# J201M1_MOS_TEST.net
KiCad netlist of a schematic drawn in Altium Designer
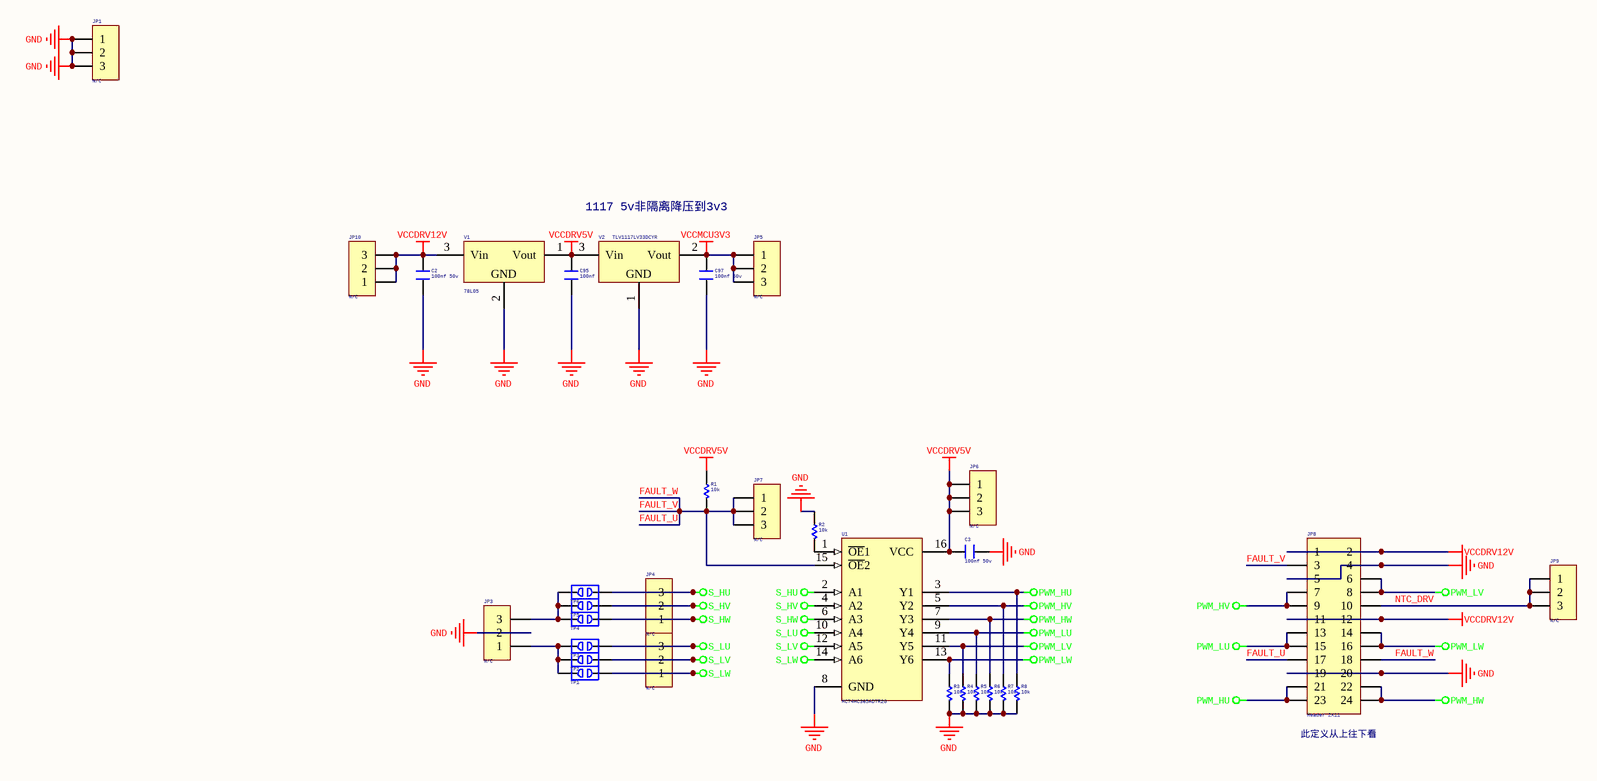
[diagram p0: J201M1_MOS_TEST.SchDoc]

(export (version "E")
  (design (tool "Eeschema 10.0.6"))
  (components
    (comp (ref "C2")
      (value "100nf 50v")
      (footprint "C 0603")
      (description "无极性贴片电容")
      (fields (field (name "VOLTAGE") "50v"))
      (libsource (lib "电阻-电容-电感") (part "C"))
    )
    (comp (ref "C3")
      (value "100nf 50v")
      (footprint "C 0603")
      (description "无极性贴片电容")
      (fields (field (name "VOLTAGE") "50v"))
      (libsource (lib "电阻-电容-电感") (part "C"))
    )
    (comp (ref "C95")
      (value "100nf 50v")
      (footprint "C 0603")
      (description "无极性贴片电容")
      (fields (field (name "VOLTAGE") "50v"))
      (libsource (lib "电阻-电容-电感") (part "C"))
    )
    (comp (ref "C97")
      (value "100nf 50v")
      (footprint "C 0603")
      (description "无极性贴片电容")
      (fields (field (name "VOLTAGE") "50v"))
      (libsource (lib "电阻-电容-电感") (part "C"))
    )
    (comp (ref "JP1")
      (value "N/C")
      (footprint "HDR-1X3")
      (description "3P接插件")
      (libsource (lib "") (part "Header 3_1"))
    )
    (comp (ref "JP2")
      (value "N/C")
      (footprint "HDR-1X3")
      (description "3P接插件")
      (libsource (lib "接插件") (part "Header 3"))
    )
    (comp (ref "JP3")
      (value "N/C")
      (footprint "HDR-1X3")
      (description "3P接插件")
      (libsource (lib "接插件") (part "Header 3"))
    )
    (comp (ref "JP4")
      (value "N/C")
      (footprint "HDR-1X3")
      (description "3P接插件")
      (libsource (lib "接插件") (part "Header 3"))
    )
    (comp (ref "JP5")
      (value "N/C")
      (footprint "HDR-1X3")
      (description "3P接插件")
      (libsource (lib "") (part "Header 3_1"))
    )
    (comp (ref "JP6")
      (value "N/C")
      (footprint "HDR-1X3")
      (description "3P接插件")
      (libsource (lib "") (part "Header 3_1"))
    )
    (comp (ref "JP7")
      (value "N/C")
      (footprint "HDR-1X3")
      (description "3P接插件")
      (libsource (lib "") (part "Header 3_1"))
    )
    (comp (ref "JP8")
      (value "Header 2X11")
      (footprint "HDR-12X2")
      (description "12*2P接插件")
      (libsource (lib "接插件") (part "Header 12X2"))
    )
    (comp (ref "JP9")
      (value "N/C")
      (footprint "HDR-1X3")
      (description "3P接插件")
      (libsource (lib "") (part "Header 3_1"))
    )
    (comp (ref "JP10")
      (value "N/C")
      (footprint "HDR-1X3")
      (description "3P接插件")
      (libsource (lib "接插件") (part "Header 3"))
    )
    (comp (ref "R1")
      (value "10k")
      (footprint "R 0805")
      (description "贴片电阻")
      (libsource (lib "电阻-电容-电感") (part "R"))
    )
    (comp (ref "R2")
      (value "10k")
      (footprint "R 0805")
      (description "贴片电阻")
      (libsource (lib "电阻-电容-电感") (part "R"))
    )
    (comp (ref "R3")
      (value "10k")
      (footprint "R 0805")
      (description "贴片电阻")
      (libsource (lib "电阻-电容-电感") (part "R"))
    )
    (comp (ref "R4")
      (value "10k")
      (footprint "R 0805")
      (description "贴片电阻")
      (libsource (lib "电阻-电容-电感") (part "R"))
    )
    (comp (ref "R5")
      (value "10k")
      (footprint "R 0805")
      (description "贴片电阻")
      (libsource (lib "电阻-电容-电感") (part "R"))
    )
    (comp (ref "R6")
      (value "10k")
      (footprint "R 0805")
      (description "贴片电阻")
      (libsource (lib "电阻-电容-电感") (part "R"))
    )
    (comp (ref "R7")
      (value "10k")
      (footprint "R 0805")
      (description "贴片电阻")
      (libsource (lib "电阻-电容-电感") (part "R"))
    )
    (comp (ref "R8")
      (value "10k")
      (footprint "R 0805")
      (description "贴片电阻")
      (libsource (lib "电阻-电容-电感") (part "R"))
    )
    (comp (ref "TP1")
      (value "DEBUG PAD")
      (footprint "DEBUG PAD 0603")
      (description "调试断点焊盘")
      (libsource (lib "未分类器件") (part "DEBUG"))
    )
    (comp (ref "TP2")
      (value "DEBUG PAD")
      (footprint "DEBUG PAD 0603")
      (description "调试断点焊盘")
      (libsource (lib "未分类器件") (part "DEBUG"))
    )
    (comp (ref "TP3")
      (value "DEBUG PAD")
      (footprint "DEBUG PAD 0603")
      (description "调试断点焊盘")
      (libsource (lib "未分类器件") (part "DEBUG"))
    )
    (comp (ref "TP4")
      (value "DEBUG PAD")
      (footprint "DEBUG PAD 0603")
      (description "调试断点焊盘")
      (libsource (lib "未分类器件") (part "DEBUG"))
    )
    (comp (ref "TP5")
      (value "DEBUG PAD")
      (footprint "DEBUG PAD 0603")
      (description "调试断点焊盘")
      (libsource (lib "未分类器件") (part "DEBUG"))
    )
    (comp (ref "TP6")
      (value "DEBUG PAD")
      (footprint "DEBUG PAD 0603")
      (description "调试断点焊盘")
      (libsource (lib "未分类器件") (part "DEBUG"))
    )
    (comp (ref "U1")
      (value "MC74HC365ADTR2G")
      (footprint "TSSOP16_L")
      (description "6路缓冲器")
      (libsource (lib "74系列芯片") (part "SN74HC365D"))
    )
    (comp (ref "V1")
      (value "78L05")
      (footprint "SOT89_M")
      (description "SOT89线性稳压芯片")
      (libsource (lib "IC芯片") (part "78LXX"))
    )
    (comp (ref "V2")
      (value "TLV1117LV33DCYR")
      (footprint "SOT223_L")
      (description "三端稳压芯片")
      (libsource (lib "IC芯片") (part "AMS1117"))
    )
  )
  (nets
    (net (code "1") (name "/FAULT_U") (class "Default")
      (node (ref "JP7") (pin "1") (pinfunction "1_1") (pintype "passive"))
      (node (ref "JP7") (pin "2") (pinfunction "2_2") (pintype "passive"))
      (node (ref "JP7") (pin "3") (pinfunction "3_3") (pintype "passive"))
      (node (ref "JP8") (pin "17") (pinfunction "17_17") (pintype "passive"))
      (node (ref "JP8") (pin "18") (pinfunction "18_18") (pintype "passive"))
      (node (ref "JP8") (pin "3") (pinfunction "3_3") (pintype "passive"))
      (node (ref "R1") (pin "2") (pinfunction "2_2") (pintype "passive"))
      (node (ref "U1") (pin "15") (pinfunction "~{OE}2_15") (pintype "input"))
    )
    (net (code "2") (name "/NTC_DRV") (class "Default")
      (node (ref "JP8") (pin "10") (pinfunction "10_10") (pintype "passive"))
      (node (ref "JP9") (pin "1") (pinfunction "1_1") (pintype "passive"))
      (node (ref "JP9") (pin "2") (pinfunction "2_2") (pintype "passive"))
      (node (ref "JP9") (pin "3") (pinfunction "3_3") (pintype "passive"))
    )
    (net (code "3") (name "GND") (class "Default")
      (node (ref "C2") (pin "2") (pinfunction "2_2") (pintype "passive"))
      (node (ref "C3") (pin "2") (pinfunction "2_2") (pintype "passive"))
      (node (ref "C95") (pin "2") (pinfunction "2_2") (pintype "passive"))
      (node (ref "C97") (pin "2") (pinfunction "2_2") (pintype "passive"))
      (node (ref "JP1") (pin "1") (pinfunction "1_1") (pintype "passive"))
      (node (ref "JP1") (pin "2") (pinfunction "2_2") (pintype "passive"))
      (node (ref "JP1") (pin "3") (pinfunction "3_3") (pintype "passive"))
      (node (ref "JP3") (pin "2") (pinfunction "2_2") (pintype "passive"))
      (node (ref "JP8") (pin "19") (pinfunction "19_19") (pintype "passive"))
      (node (ref "JP8") (pin "20") (pinfunction "20_20") (pintype "passive"))
      (node (ref "JP8") (pin "4") (pinfunction "4_4") (pintype "passive"))
      (node (ref "JP8") (pin "5") (pinfunction "5_5") (pintype "passive"))
      (node (ref "R2") (pin "1") (pinfunction "1_1") (pintype "passive"))
      (node (ref "R3") (pin "2") (pinfunction "2_2") (pintype "passive"))
      (node (ref "R4") (pin "2") (pinfunction "2_2") (pintype "passive"))
      (node (ref "R5") (pin "2") (pinfunction "2_2") (pintype "passive"))
      (node (ref "R6") (pin "2") (pinfunction "2_2") (pintype "passive"))
      (node (ref "R7") (pin "2") (pinfunction "2_2") (pintype "passive"))
      (node (ref "R8") (pin "2") (pinfunction "2_2") (pintype "passive"))
      (node (ref "U1") (pin "8") (pinfunction "GND_8") (pintype "power_in"))
      (node (ref "V1") (pin "2") (pinfunction "GND_2") (pintype "passive"))
      (node (ref "V2") (pin "1") (pinfunction "GND_1") (pintype "passive"))
    )
    (net (code "4") (name "Net-(JP3-Pad1)") (class "Default")
      (node (ref "JP3") (pin "1") (pinfunction "1_1") (pintype "passive"))
      (node (ref "TP1") (pin "2") (pinfunction "2_2") (pintype "passive"))
      (node (ref "TP2") (pin "2") (pinfunction "2_2") (pintype "passive"))
      (node (ref "TP3") (pin "2") (pinfunction "2_2") (pintype "passive"))
    )
    (net (code "5") (name "Net-(JP3-Pad3)") (class "Default")
      (node (ref "JP3") (pin "3") (pinfunction "3_3") (pintype "passive"))
      (node (ref "TP4") (pin "2") (pinfunction "2_2") (pintype "passive"))
      (node (ref "TP5") (pin "2") (pinfunction "2_2") (pintype "passive"))
      (node (ref "TP6") (pin "2") (pinfunction "2_2") (pintype "passive"))
    )
    (net (code "6") (name "Net-(U1-~{OE}1)") (class "Default")
      (node (ref "R2") (pin "2") (pinfunction "2_2") (pintype "passive"))
      (node (ref "U1") (pin "1") (pinfunction "~{OE}1_1") (pintype "input"))
    )
    (net (code "7") (name "PWM_HU") (class "Default")
      (node (ref "JP8") (pin "21") (pinfunction "21_21") (pintype "passive"))
      (node (ref "JP8") (pin "23") (pinfunction "23_23") (pintype "passive"))
      (node (ref "R8") (pin "1") (pinfunction "1_1") (pintype "passive"))
      (node (ref "U1") (pin "3") (pinfunction "Y1_3") (pintype "tri_state"))
    )
    (net (code "8") (name "PWM_HV") (class "Default")
      (node (ref "JP8") (pin "7") (pinfunction "7_7") (pintype "passive"))
      (node (ref "JP8") (pin "9") (pinfunction "9_9") (pintype "passive"))
      (node (ref "R7") (pin "1") (pinfunction "1_1") (pintype "passive"))
      (node (ref "U1") (pin "5") (pinfunction "Y2_5") (pintype "tri_state"))
    )
    (net (code "9") (name "PWM_HW") (class "Default")
      (node (ref "JP8") (pin "22") (pinfunction "22_22") (pintype "passive"))
      (node (ref "JP8") (pin "24") (pinfunction "24_24") (pintype "passive"))
      (node (ref "R6") (pin "1") (pinfunction "1_1") (pintype "passive"))
      (node (ref "U1") (pin "7") (pinfunction "Y3_7") (pintype "tri_state"))
    )
    (net (code "10") (name "PWM_LU") (class "Default")
      (node (ref "JP8") (pin "13") (pinfunction "13_13") (pintype "passive"))
      (node (ref "JP8") (pin "15") (pinfunction "15_15") (pintype "passive"))
      (node (ref "R5") (pin "1") (pinfunction "1_1") (pintype "passive"))
      (node (ref "U1") (pin "9") (pinfunction "Y4_9") (pintype "tri_state"))
    )
    (net (code "11") (name "PWM_LV") (class "Default")
      (node (ref "JP8") (pin "6") (pinfunction "6_6") (pintype "passive"))
      (node (ref "JP8") (pin "8") (pinfunction "8_8") (pintype "passive"))
      (node (ref "R4") (pin "1") (pinfunction "1_1") (pintype "passive"))
      (node (ref "U1") (pin "11") (pinfunction "Y5_11") (pintype "tri_state"))
    )
    (net (code "12") (name "PWM_LW") (class "Default")
      (node (ref "JP8") (pin "14") (pinfunction "14_14") (pintype "passive"))
      (node (ref "JP8") (pin "16") (pinfunction "16_16") (pintype "passive"))
      (node (ref "R3") (pin "1") (pinfunction "1_1") (pintype "passive"))
      (node (ref "U1") (pin "13") (pinfunction "Y6_13") (pintype "tri_state"))
    )
    (net (code "13") (name "S_HU") (class "Default")
      (node (ref "JP4") (pin "3") (pinfunction "3_3") (pintype "passive"))
      (node (ref "TP6") (pin "1") (pinfunction "1_1") (pintype "passive"))
      (node (ref "U1") (pin "2") (pinfunction "A1_2") (pintype "input"))
    )
    (net (code "14") (name "S_HV") (class "Default")
      (node (ref "JP4") (pin "2") (pinfunction "2_2") (pintype "passive"))
      (node (ref "TP5") (pin "1") (pinfunction "1_1") (pintype "passive"))
      (node (ref "U1") (pin "4") (pinfunction "A2_4") (pintype "input"))
    )
    (net (code "15") (name "S_HW") (class "Default")
      (node (ref "JP4") (pin "1") (pinfunction "1_1") (pintype "passive"))
      (node (ref "TP4") (pin "1") (pinfunction "1_1") (pintype "passive"))
      (node (ref "U1") (pin "6") (pinfunction "A3_6") (pintype "input"))
    )
    (net (code "16") (name "S_LU") (class "Default")
      (node (ref "JP2") (pin "3") (pinfunction "3_3") (pintype "passive"))
      (node (ref "TP3") (pin "1") (pinfunction "1_1") (pintype "passive"))
      (node (ref "U1") (pin "10") (pinfunction "A4_10") (pintype "input"))
    )
    (net (code "17") (name "S_LV") (class "Default")
      (node (ref "JP2") (pin "2") (pinfunction "2_2") (pintype "passive"))
      (node (ref "TP2") (pin "1") (pinfunction "1_1") (pintype "passive"))
      (node (ref "U1") (pin "12") (pinfunction "A5_12") (pintype "input"))
    )
    (net (code "18") (name "S_LW") (class "Default")
      (node (ref "JP2") (pin "1") (pinfunction "1_1") (pintype "passive"))
      (node (ref "TP1") (pin "1") (pinfunction "1_1") (pintype "passive"))
      (node (ref "U1") (pin "14") (pinfunction "A6_14") (pintype "input"))
    )
    (net (code "19") (name "VCCDRV5V") (class "Default")
      (node (ref "C3") (pin "1") (pinfunction "1_1") (pintype "passive"))
      (node (ref "C95") (pin "1") (pinfunction "1_1") (pintype "passive"))
      (node (ref "JP6") (pin "1") (pinfunction "1_1") (pintype "passive"))
      (node (ref "JP6") (pin "2") (pinfunction "2_2") (pintype "passive"))
      (node (ref "JP6") (pin "3") (pinfunction "3_3") (pintype "passive"))
      (node (ref "R1") (pin "1") (pinfunction "1_1") (pintype "passive"))
      (node (ref "U1") (pin "16") (pinfunction "VCC_16") (pintype "power_in"))
      (node (ref "V1") (pin "1") (pinfunction "Vout_1") (pintype "passive"))
      (node (ref "V2") (pin "3") (pinfunction "Vin_3") (pintype "passive"))
    )
    (net (code "20") (name "VCCDRV12V") (class "Default")
      (node (ref "C2") (pin "1") (pinfunction "1_1") (pintype "passive"))
      (node (ref "JP10") (pin "1") (pinfunction "1_1") (pintype "passive"))
      (node (ref "JP10") (pin "2") (pinfunction "2_2") (pintype "passive"))
      (node (ref "JP10") (pin "3") (pinfunction "3_3") (pintype "passive"))
      (node (ref "JP8") (pin "1") (pinfunction "1_1") (pintype "passive"))
      (node (ref "JP8") (pin "11") (pinfunction "11_11") (pintype "passive"))
      (node (ref "JP8") (pin "12") (pinfunction "12_12") (pintype "passive"))
      (node (ref "JP8") (pin "2") (pinfunction "2_2") (pintype "passive"))
      (node (ref "V1") (pin "3") (pinfunction "Vin_3") (pintype "passive"))
    )
    (net (code "21") (name "VCCMCU3V3") (class "Default")
      (node (ref "C97") (pin "1") (pinfunction "1_1") (pintype "passive"))
      (node (ref "JP5") (pin "1") (pinfunction "1_1") (pintype "passive"))
      (node (ref "JP5") (pin "2") (pinfunction "2_2") (pintype "passive"))
      (node (ref "JP5") (pin "3") (pinfunction "3_3") (pintype "passive"))
      (node (ref "V2") (pin "2") (pinfunction "Vout_2") (pintype "passive"))
    )
  )
)
